# FT232.net
KiCad netlist of a schematic drawn in Altium Designer
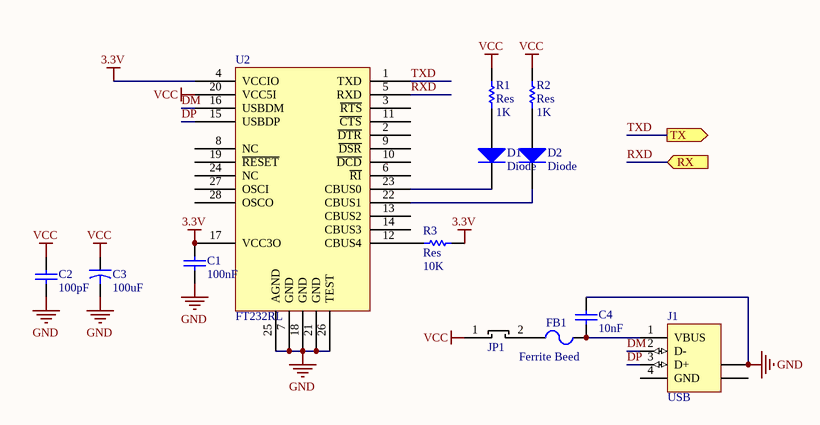
[diagram p0: FT232.SchDoc]

(export (version "E")
  (design (tool "Eeschema 10.0.6"))
  (components
    (comp (ref "C1")
      (value "100nF")
      (footprint "2012[0805]")
      (description "Capacitor")
      (fields (field (name "Comment") "Cap_UP") (field (name "PUBLISHER") "Altium Limited"))
      (libsource (lib "KN2CLib") (part "Cap_UP"))
    )
    (comp (ref "C2")
      (value "100pF")
      (footprint "2012[0805]")
      (description "Capacitor")
      (fields (field (name "Comment") "Cap_UP") (field (name "PUBLISHER") "Altium Limited"))
      (libsource (lib "KN2CLib") (part "Cap_UP"))
    )
    (comp (ref "C3")
      (value "100uF")
      (footprint "2012[0805]")
      (description "Capacitor")
      (fields (field (name "Comment") "Cap_El") (field (name "PUBLISHER") "Altium Limited"))
      (libsource (lib "KN2CLib") (part "Cap_El"))
    )
    (comp (ref "C4")
      (value "10nF")
      (footprint "2012[0805]")
      (description "Capacitor")
      (fields (field (name "Comment") "Cap_UP") (field (name "PUBLISHER") "Altium Limited"))
      (libsource (lib "KN2CLib") (part "Cap_UP"))
    )
    (comp (ref "D1")
      (value "Diode")
      (footprint "2012[0805]")
      (description "1 Amp General Purpose Rectifier")
      (fields (field (name "PUBLISHER") "Altium Limited"))
      (libsource (lib "KN2CLib") (part "Diode"))
    )
    (comp (ref "D2")
      (value "Diode")
      (footprint "2012[0805]")
      (description "1 Amp General Purpose Rectifier")
      (fields (field (name "PUBLISHER") "Altium Limited"))
      (libsource (lib "KN2CLib") (part "Diode"))
    )
    (comp (ref "FB1")
      (value "Ferrite Beed")
      (footprint "2012[0805]")
      (fields (field (name "PUBLISHER") "Altium Limited"))
      (libsource (lib "KN2CLib") (part "Ferrite Beed"))
    )
    (comp (ref "J1")
      (value "USB")
      (footprint "USB_MINI")
      (description "USB 1.1, Right Angle, Thru-Hole, A Type, Receptacle, 4 Position, Black")
      (fields (field (name "PUBLISHER") "Altium Limited"))
      (libsource (lib "KN2CLib") (part "USB"))
    )
    (comp (ref "JP1") (value "JUMPER") (footprint "HDR1X2") (libsource (lib "KN2CLib") (part "JUMPER")))
    (comp (ref "R1")
      (value "Res")
      (footprint "2012[0805]")
      (description "Semiconductor Resistor")
      (fields (field (name "ALTIUM_VALUE") "1K") (field (name "PUBLISHER") "Altium Limited"))
      (libsource (lib "KN2CLib") (part "Res"))
    )
    (comp (ref "R2")
      (value "Res")
      (footprint "2012[0805]")
      (description "Semiconductor Resistor")
      (fields (field (name "ALTIUM_VALUE") "1K") (field (name "PUBLISHER") "Altium Limited"))
      (libsource (lib "KN2CLib") (part "Res"))
    )
    (comp (ref "R3")
      (value "Res")
      (footprint "2012[0805]")
      (description "Semiconductor Resistor")
      (fields (field (name "ALTIUM_VALUE") "10K") (field (name "PUBLISHER") "Altium Limited"))
      (libsource (lib "KN2CLib") (part "Res"))
    )
    (comp (ref "U2") (value "FT232RL") (footprint "SSOP28") (libsource (lib "KN2CLib") (part "FT232RL")))
  )
  (nets
    (net (code "1") (name "/DM") (class "Default")
      (node (ref "J1") (pin "2") (pinfunction "D-_2") (pintype "bidirectional"))
      (node (ref "U2") (pin "16") (pinfunction "USBDM_16") (pintype "passive"))
    )
    (net (code "2") (name "/DP") (class "Default")
      (node (ref "J1") (pin "3") (pinfunction "D+_3") (pintype "bidirectional"))
      (node (ref "U2") (pin "15") (pinfunction "USBDP_15") (pintype "passive"))
    )
    (net (code "3") (name "/RXD") (class "Default")
      (node (ref "U2") (pin "5") (pinfunction "RXD_5") (pintype "passive"))
    )
    (net (code "4") (name "/TXD") (class "Default")
      (node (ref "U2") (pin "1") (pinfunction "TXD_1") (pintype "passive"))
    )
    (net (code "5") (name "3.3V") (class "Default")
      (node (ref "C1") (pin "2") (pinfunction "2_2") (pintype "passive"))
      (node (ref "R3") (pin "2") (pinfunction "2_2") (pintype "passive"))
      (node (ref "U2") (pin "17") (pinfunction "VCC3O_17") (pintype "passive"))
      (node (ref "U2") (pin "4") (pinfunction "VCCIO_4") (pintype "passive"))
    )
    (net (code "6") (name "GND") (class "Default")
      (node (ref "C1") (pin "1") (pinfunction "1_1") (pintype "passive"))
      (node (ref "C2") (pin "1") (pinfunction "1_1") (pintype "passive"))
      (node (ref "C3") (pin "2") (pinfunction "2_2") (pintype "passive"))
      (node (ref "C4") (pin "1") (pinfunction "1_1") (pintype "passive"))
      (node (ref "J1") (pin "5") (pinfunction "SHLD_5") (pintype "passive"))
      (node (ref "U2") (pin "18") (pinfunction "GND_18") (pintype "passive"))
      (node (ref "U2") (pin "21") (pinfunction "GND_21") (pintype "passive"))
      (node (ref "U2") (pin "25") (pinfunction "AGND_25") (pintype "passive"))
      (node (ref "U2") (pin "26") (pinfunction "TEST_26") (pintype "passive"))
      (node (ref "U2") (pin "7") (pinfunction "GND_7") (pintype "passive"))
    )
    (net (code "7") (name "Net-(D1-A)") (class "Default")
      (node (ref "D1") (pin "1") (pinfunction "A_1") (pintype "passive"))
      (node (ref "R1") (pin "1") (pinfunction "1_1") (pintype "passive"))
    )
    (net (code "8") (name "Net-(D1-K)") (class "Default")
      (node (ref "D1") (pin "2") (pinfunction "K_2") (pintype "passive"))
      (node (ref "U2") (pin "23") (pinfunction "CBUS0_23") (pintype "passive"))
    )
    (net (code "9") (name "Net-(D2-A)") (class "Default")
      (node (ref "D2") (pin "1") (pinfunction "A_1") (pintype "passive"))
      (node (ref "R2") (pin "1") (pinfunction "1_1") (pintype "passive"))
    )
    (net (code "10") (name "Net-(D2-K)") (class "Default")
      (node (ref "D2") (pin "2") (pinfunction "K_2") (pintype "passive"))
      (node (ref "U2") (pin "22") (pinfunction "CBUS1_22") (pintype "passive"))
    )
    (net (code "11") (name "Net-(FB1-Pad1)") (class "Default")
      (node (ref "FB1") (pin "1") (pinfunction "1_1") (pintype "passive"))
      (node (ref "JP1") (pin "2") (pinfunction "2_2") (pintype "passive"))
    )
    (net (code "12") (name "Net-(J1-VBUS)") (class "Default")
      (node (ref "C4") (pin "2") (pinfunction "2_2") (pintype "passive"))
      (node (ref "FB1") (pin "2") (pinfunction "2_2") (pintype "passive"))
      (node (ref "J1") (pin "1") (pinfunction "VBUS_1") (pintype "power_in"))
    )
    (net (code "13") (name "Net-(U2-CBUS4)") (class "Default")
      (node (ref "R3") (pin "1") (pinfunction "1_1") (pintype "passive"))
      (node (ref "U2") (pin "12") (pinfunction "CBUS4_12") (pintype "passive"))
    )
    (net (code "14") (name "VCC") (class "Default")
      (node (ref "C2") (pin "2") (pinfunction "2_2") (pintype "passive"))
      (node (ref "C3") (pin "1") (pinfunction "1_1") (pintype "passive"))
      (node (ref "JP1") (pin "1") (pinfunction "1_1") (pintype "passive"))
      (node (ref "R1") (pin "2") (pinfunction "2_2") (pintype "passive"))
      (node (ref "R2") (pin "2") (pinfunction "2_2") (pintype "passive"))
      (node (ref "U2") (pin "20") (pinfunction "VCC5I_20") (pintype "passive"))
    )
    (net (code "15") (name "unconnected-(J1-GND-Pad4)") (class "Default")
      (node (ref "J1") (pin "4") (pinfunction "GND_4") (pintype "power_in"))
    )
    (net (code "16") (name "unconnected-(J1-SHLD-Pad6)") (class "Default")
      (node (ref "J1") (pin "6") (pinfunction "SHLD_6") (pintype "passive"))
    )
    (net (code "17") (name "unconnected-(U2-CBUS2-Pad13)") (class "Default")
      (node (ref "U2") (pin "13") (pinfunction "CBUS2_13") (pintype "passive"))
    )
    (net (code "18") (name "unconnected-(U2-CBUS3-Pad14)") (class "Default")
      (node (ref "U2") (pin "14") (pinfunction "CBUS3_14") (pintype "passive"))
    )
    (net (code "19") (name "unconnected-(U2-NC-Pad8)") (class "Default")
      (node (ref "U2") (pin "8") (pinfunction "NC_8") (pintype "passive"))
    )
    (net (code "20") (name "unconnected-(U2-NC-Pad24)") (class "Default")
      (node (ref "U2") (pin "24") (pinfunction "NC_24") (pintype "passive"))
    )
    (net (code "21") (name "unconnected-(U2-OSCI-Pad27)") (class "Default")
      (node (ref "U2") (pin "27") (pinfunction "OSCI_27") (pintype "passive"))
    )
    (net (code "22") (name "unconnected-(U2-OSCO-Pad28)") (class "Default")
      (node (ref "U2") (pin "28") (pinfunction "OSCO_28") (pintype "passive"))
    )
    (net (code "23") (name "unconnected-(U2-~{CTS}-Pad11)") (class "Default")
      (node (ref "U2") (pin "11") (pinfunction "~{CTS}_11") (pintype "passive"))
    )
    (net (code "24") (name "unconnected-(U2-~{DCD}-Pad10)") (class "Default")
      (node (ref "U2") (pin "10") (pinfunction "~{DCD}_10") (pintype "passive"))
    )
    (net (code "25") (name "unconnected-(U2-~{DSR}-Pad9)") (class "Default")
      (node (ref "U2") (pin "9") (pinfunction "~{DSR}_9") (pintype "passive"))
    )
    (net (code "26") (name "unconnected-(U2-~{DTR}-Pad2)") (class "Default")
      (node (ref "U2") (pin "2") (pinfunction "~{DTR}_2") (pintype "passive"))
    )
    (net (code "27") (name "unconnected-(U2-~{RESET}-Pad19)") (class "Default")
      (node (ref "U2") (pin "19") (pinfunction "~{RESET}_19") (pintype "passive"))
    )
    (net (code "28") (name "unconnected-(U2-~{RI}-Pad6)") (class "Default")
      (node (ref "U2") (pin "6") (pinfunction "~{RI}_6") (pintype "passive"))
    )
    (net (code "29") (name "unconnected-(U2-~{RTS}-Pad3)") (class "Default")
      (node (ref "U2") (pin "3") (pinfunction "~{RTS}_3") (pintype "passive"))
    )
  )
)
